# waves_v20.net
KiCad netlist of a schematic drawn in EAGLE
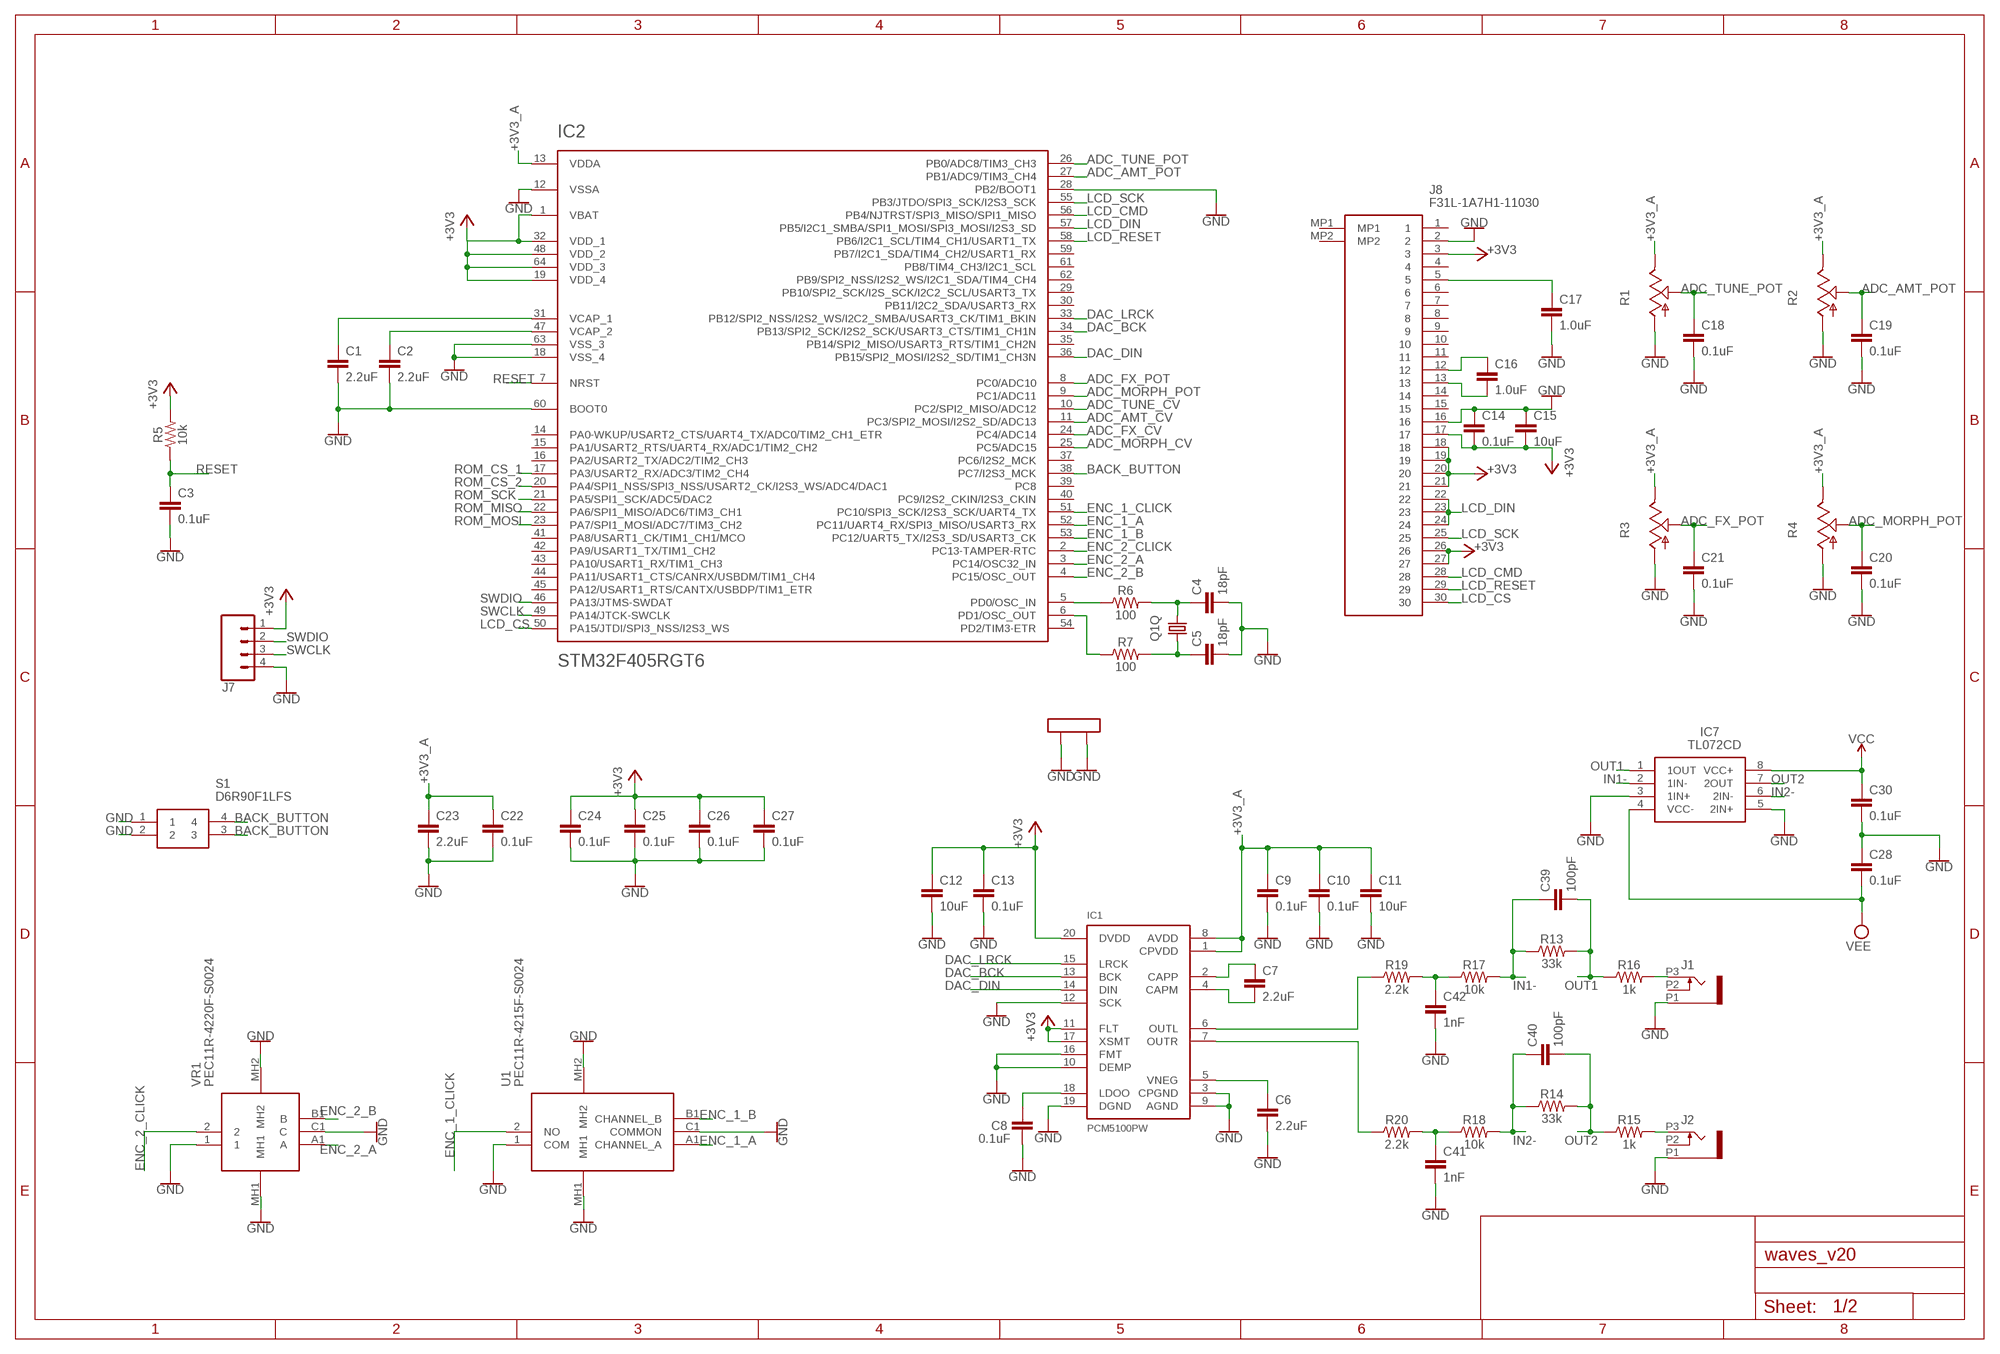
[diagram p0: schematic, sheet 1]
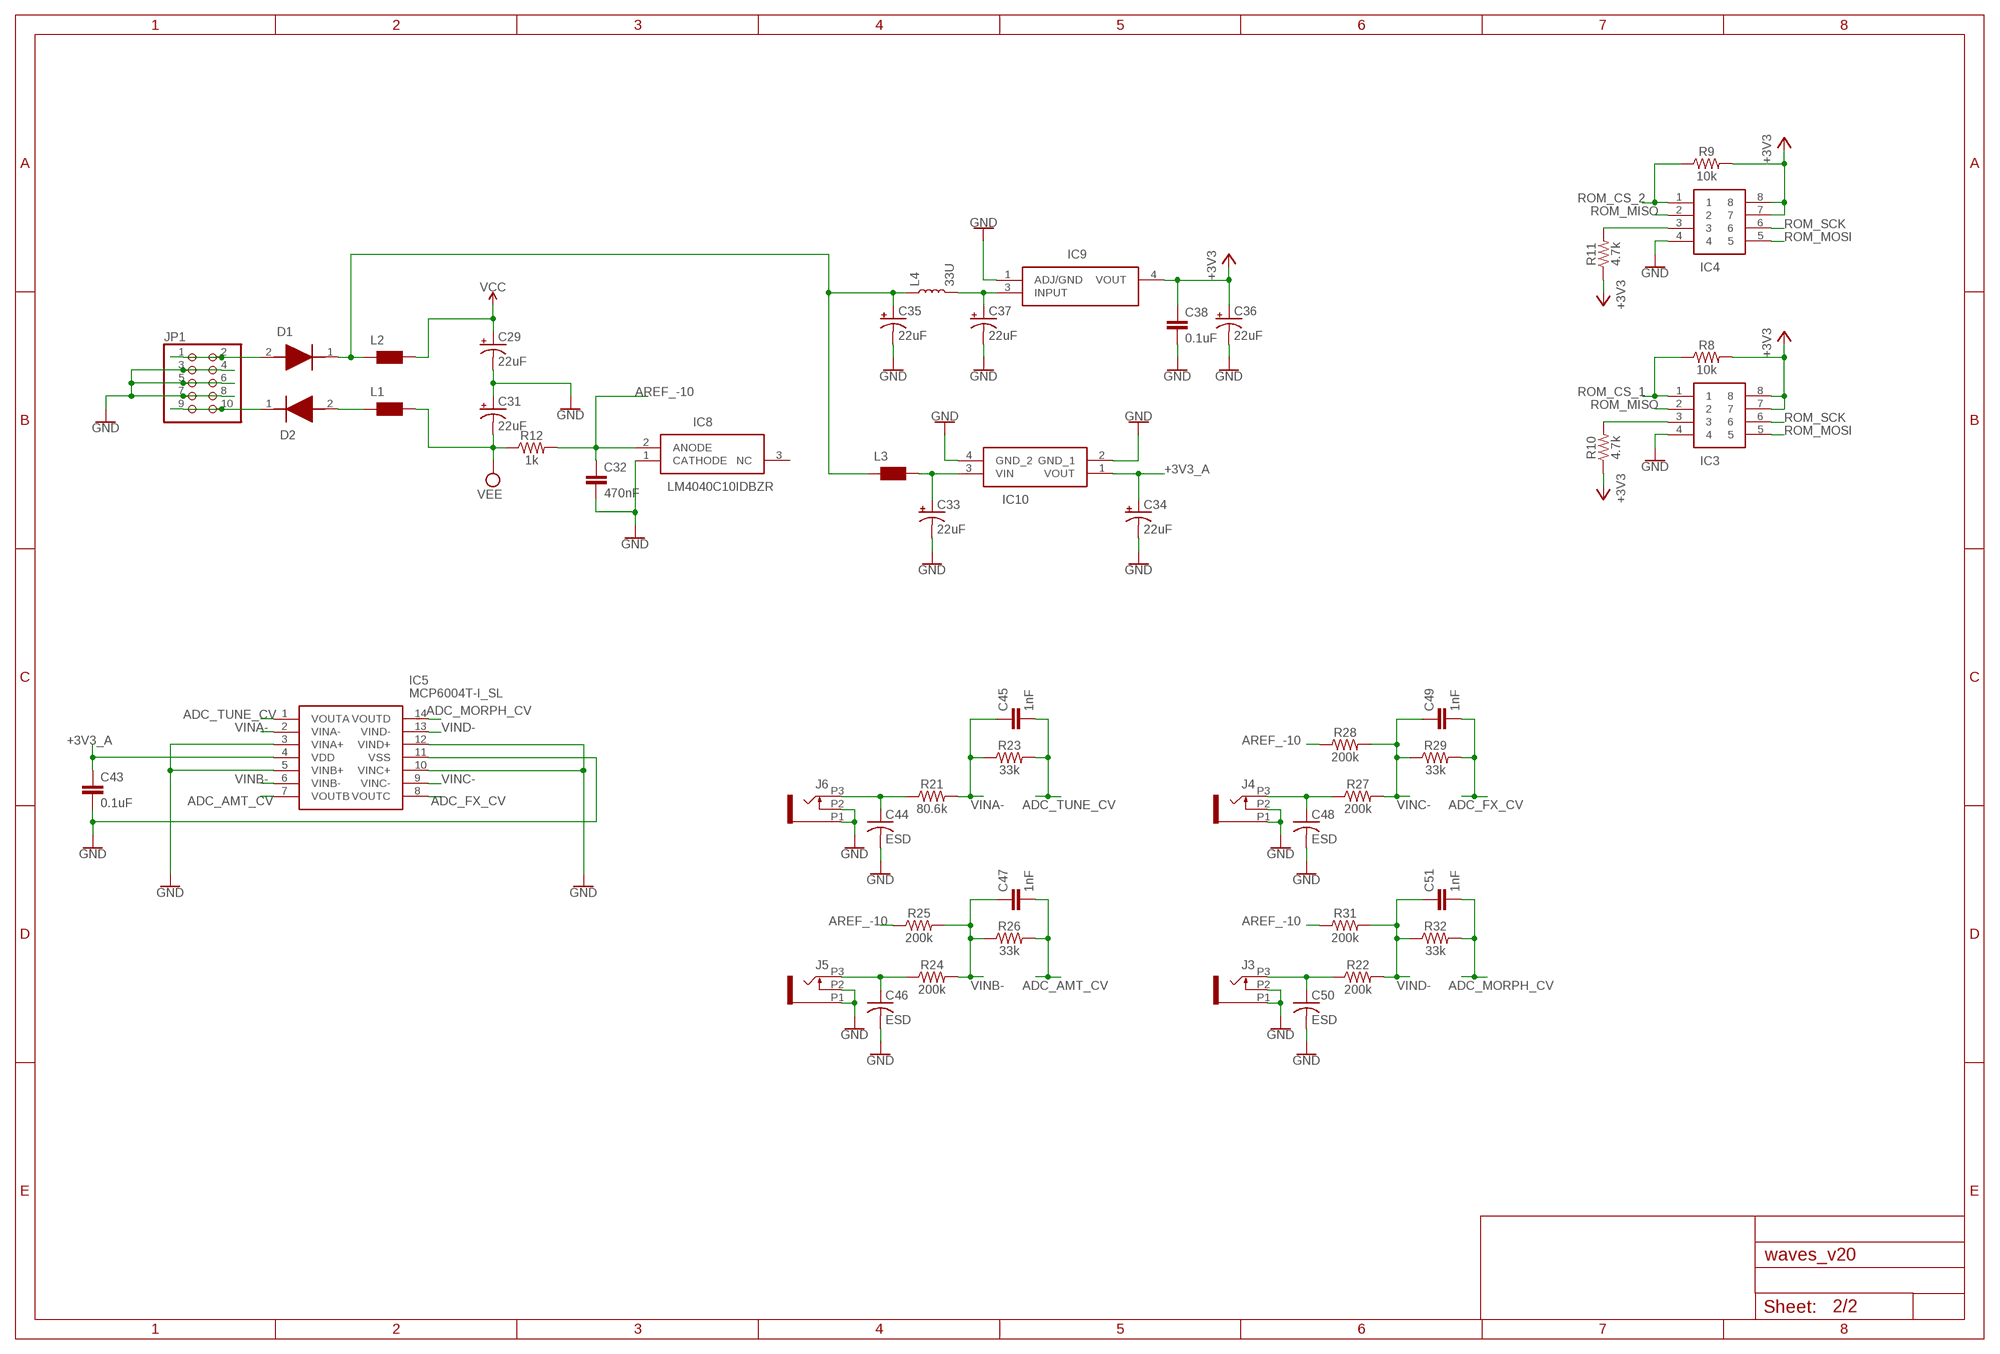
[diagram p1: schematic, sheet 2]

(export (version "E")
  (design (tool "Eeschema 10.0.6"))
  (components
    (comp (ref "C29")
      (value "22uF")
      (footprint "eagle-import:PANASONIC_C")
      (libsource (lib "eagle-import") (part "22UF-POLAR-PANASONIC_C-35V-20%"))
    )
    (comp (ref "C31")
      (value "22uF")
      (footprint "eagle-import:PANASONIC_C")
      (libsource (lib "eagle-import") (part "22UF-POLAR-PANASONIC_C-35V-20%"))
    )
    (comp (ref "C32")
      (value "470nF")
      (footprint "eagle-import:0402")
      (libsource (lib "eagle-import") (part "470NF-0402-16V-10%"))
    )
    (comp (ref "C33")
      (value "22uF")
      (footprint "eagle-import:PANASONIC_C")
      (libsource (lib "eagle-import") (part "22UF-POLAR-PANASONIC_C-35V-20%"))
    )
    (comp (ref "C34")
      (value "22uF")
      (footprint "eagle-import:PANASONIC_C")
      (libsource (lib "eagle-import") (part "22UF-POLAR-PANASONIC_C-35V-20%"))
    )
    (comp (ref "C35")
      (value "22uF")
      (footprint "eagle-import:PANASONIC_C")
      (libsource (lib "eagle-import") (part "22UF-POLAR-PANASONIC_C-35V-20%"))
    )
    (comp (ref "C36")
      (value "22uF")
      (footprint "eagle-import:PANASONIC_C")
      (libsource (lib "eagle-import") (part "22UF-POLAR-PANASONIC_C-35V-20%"))
    )
    (comp (ref "C37")
      (value "22uF")
      (footprint "eagle-import:PANASONIC_C")
      (libsource (lib "eagle-import") (part "22UF-POLAR-PANASONIC_C-35V-20%"))
    )
    (comp (ref "C38")
      (value "0.1uF")
      (footprint "eagle-import:0603")
      (libsource (lib "eagle-import") (part "0.1UF-0603-25V-(+80/-20%)"))
    )
    (comp (ref "C43")
      (value "0.1uF")
      (footprint "eagle-import:0603")
      (libsource (lib "eagle-import") (part "0.1UF-0603-25V-(+80/-20%)"))
    )
    (comp (ref "C44")
      (value "ESD")
      (footprint "eagle-import:C0603")
      (libsource (lib "eagle-import") (part "C-USC0603"))
    )
    (comp (ref "C45")
      (value "1nF")
      (footprint "eagle-import:0603")
      (libsource (lib "eagle-import") (part "1.0NF/1000PF-0603-50V-10%"))
    )
    (comp (ref "C46")
      (value "ESD")
      (footprint "eagle-import:C0603")
      (libsource (lib "eagle-import") (part "C-USC0603"))
    )
    (comp (ref "C47")
      (value "1nF")
      (footprint "eagle-import:0603")
      (libsource (lib "eagle-import") (part "1.0NF/1000PF-0603-50V-10%"))
    )
    (comp (ref "C48")
      (value "ESD")
      (footprint "eagle-import:C0603")
      (libsource (lib "eagle-import") (part "C-USC0603"))
    )
    (comp (ref "C49")
      (value "1nF")
      (footprint "eagle-import:0603")
      (libsource (lib "eagle-import") (part "1.0NF/1000PF-0603-50V-10%"))
    )
    (comp (ref "C50")
      (value "ESD")
      (footprint "eagle-import:C0603")
      (libsource (lib "eagle-import") (part "C-USC0603"))
    )
    (comp (ref "C51")
      (value "1nF")
      (footprint "eagle-import:0603")
      (libsource (lib "eagle-import") (part "1.0NF/1000PF-0603-50V-10%"))
    )
    (comp (ref "D1")
      (value "1N5819HW-7-F")
      (footprint "eagle-import:SOD3716X145N")
      (fields (field (name "MOUSER_PART_NUMBER") "621-1N5819HW-F"))
      (libsource (lib "eagle-import") (part "1N5819HW-7-F"))
    )
    (comp (ref "D2")
      (value "1N5819HW-7-F")
      (footprint "eagle-import:SOD3716X145N")
      (fields (field (name "MOUSER_PART_NUMBER") "621-1N5819HW-F"))
      (libsource (lib "eagle-import") (part "1N5819HW-7-F"))
    )
    (comp (ref "IC3")
      (value "1-2199298-2")
      (footprint "eagle-import:DIPS762W70P254L1016H510Q8N")
      (fields (field (name "MOUSER_PART_NUMBER") "571-1-2199298-2"))
      (libsource (lib "eagle-import") (part "1-2199298-2"))
    )
    (comp (ref "IC4")
      (value "1-2199298-2")
      (footprint "eagle-import:DIPS762W70P254L1016H510Q8N")
      (fields (field (name "MOUSER_PART_NUMBER") "571-1-2199298-2"))
      (libsource (lib "eagle-import") (part "1-2199298-2"))
    )
    (comp (ref "IC5")
      (value "MCP6004T-I_SL")
      (footprint "eagle-import:SOIC127P600X175-14N")
      (fields
        (field (name "MANUFACTURER_PART_NUMBER") "MCP6004T-I/SL")
        (field (name "MOUSER_PART_NUMBER") "579-MCP6004T-I/SL")
      )
      (libsource (lib "eagle-import") (part "MCP6004T-I_SL"))
    )
    (comp (ref "IC8")
      (value "LM4040C10IDBZR")
      (footprint "eagle-import:SOT95P237X112-3N")
      (fields (field (name "MOUSER_PART_NUMBER") "595-LM4040C10IDBZR"))
      (libsource (lib "eagle-import") (part "LM4040C10IDBZR"))
    )
    (comp (ref "IC9")
      (value "LM1117DT-3.3_NOPB")
      (footprint "eagle-import:TO228P991X238-3N")
      (fields
        (field (name "MANUFACTURER_PART_NUMBER") "LM1117DT-3.3/NOPB")
        (field (name "MOUSER_PART_NUMBER") "926-LM1117DT-3.3NOPB")
      )
      (libsource (lib "eagle-import") (part "LM1117DT-3.3_NOPB"))
    )
    (comp (ref "IC10")
      (value "LD2981ABU33TR")
      (footprint "eagle-import:LD2981ABU33TR")
      (fields (field (name "MOUSER_PART_NUMBER") "511-LD2981ABU33"))
      (libsource (lib "eagle-import") (part "LD2981ABU33TR"))
    )
    (comp (ref "J3")
      (value "PJ301_THONKICONN6")
      (footprint "eagle-import:WQP_PJ_301M6")
      (libsource (lib "eagle-import") (part "PJ301_THONKICONN6"))
    )
    (comp (ref "J4")
      (value "PJ301_THONKICONN6")
      (footprint "eagle-import:WQP_PJ_301M6")
      (libsource (lib "eagle-import") (part "PJ301_THONKICONN6"))
    )
    (comp (ref "J5")
      (value "PJ301_THONKICONN6")
      (footprint "eagle-import:WQP_PJ_301M6")
      (libsource (lib "eagle-import") (part "PJ301_THONKICONN6"))
    )
    (comp (ref "J6")
      (value "PJ301_THONKICONN6")
      (footprint "eagle-import:WQP_PJ_301M6")
      (libsource (lib "eagle-import") (part "PJ301_THONKICONN6"))
    )
    (comp (ref "JP1")
      (value "PINHD-2X5")
      (footprint "eagle-import:2X05")
      (libsource (lib "eagle-import") (part "PINHD-2X5"))
    )
    (comp (ref "L1")
      (value "WE-CBF_0603")
      (footprint "eagle-import:0603")
      (libsource (lib "eagle-import") (part "WE-CBF_0603"))
    )
    (comp (ref "L2")
      (value "WE-CBF_0603")
      (footprint "eagle-import:0603")
      (libsource (lib "eagle-import") (part "WE-CBF_0603"))
    )
    (comp (ref "L3")
      (value "WE-CBF_0603")
      (footprint "eagle-import:0603")
      (libsource (lib "eagle-import") (part "WE-CBF_0603"))
    )
    (comp (ref "L4")
      (value "33U")
      (footprint "eagle-import:0805")
      (libsource (lib "eagle-import") (part "INDUCTOR-0805-3.3UH"))
    )
    (comp (ref "R8")
      (value "10k")
      (footprint "eagle-import:0603")
      (libsource (lib "eagle-import") (part "10KOHM-0603-1/10W-1%"))
    )
    (comp (ref "R9")
      (value "10k")
      (footprint "eagle-import:0603")
      (libsource (lib "eagle-import") (part "10KOHM-0603-1/10W-1%"))
    )
    (comp (ref "R10")
      (value "4.7k")
      (footprint "eagle-import:0603")
      (libsource (lib "eagle-import") (part "4.7KOHM-0603-1/10W-1%"))
    )
    (comp (ref "R11")
      (value "4.7k")
      (footprint "eagle-import:0603")
      (libsource (lib "eagle-import") (part "4.7KOHM-0603-1/10W-1%"))
    )
    (comp (ref "R12")
      (value "1k")
      (footprint "eagle-import:0603")
      (libsource (lib "eagle-import") (part "1KOHM-0603-1/10W-1%"))
    )
    (comp (ref "R21")
      (value "80.6k")
      (footprint "eagle-import:0603")
      (libsource (lib "eagle-import") (part "82OHM-0603-1/10W-1%"))
    )
    (comp (ref "R22")
      (value "200k")
      (footprint "eagle-import:0603")
      (libsource (lib "eagle-import") (part "200KOHM-0603-1/10W-1%"))
    )
    (comp (ref "R23")
      (value "33k")
      (footprint "eagle-import:0603")
      (libsource (lib "eagle-import") (part "33KOHM-0603-1/10W-1%"))
    )
    (comp (ref "R24")
      (value "200k")
      (footprint "eagle-import:0603")
      (libsource (lib "eagle-import") (part "200KOHM-0603-1/10W-1%"))
    )
    (comp (ref "R25")
      (value "200k")
      (footprint "eagle-import:0603")
      (libsource (lib "eagle-import") (part "200KOHM-0603-1/10W-1%"))
    )
    (comp (ref "R26")
      (value "33k")
      (footprint "eagle-import:0603")
      (libsource (lib "eagle-import") (part "33KOHM-0603-1/10W-1%"))
    )
    (comp (ref "R27")
      (value "200k")
      (footprint "eagle-import:0603")
      (libsource (lib "eagle-import") (part "200KOHM-0603-1/10W-1%"))
    )
    (comp (ref "R28")
      (value "200k")
      (footprint "eagle-import:0603")
      (libsource (lib "eagle-import") (part "200KOHM-0603-1/10W-1%"))
    )
    (comp (ref "R29")
      (value "33k")
      (footprint "eagle-import:0603")
      (libsource (lib "eagle-import") (part "33KOHM-0603-1/10W-1%"))
    )
    (comp (ref "R31")
      (value "200k")
      (footprint "eagle-import:0603")
      (libsource (lib "eagle-import") (part "200KOHM-0603-1/10W-1%"))
    )
    (comp (ref "R32")
      (value "33k")
      (footprint "eagle-import:0603")
      (libsource (lib "eagle-import") (part "33KOHM-0603-1/10W-1%"))
    )
    (comp (ref "C1")
      (value "2.2uF")
      (footprint "eagle-import:0603")
      (libsource (lib "eagle-import") (part "2.2UF-0603-10V-20%"))
    )
    (comp (ref "C2")
      (value "2.2uF")
      (footprint "eagle-import:0603")
      (libsource (lib "eagle-import") (part "2.2UF-0603-10V-20%"))
    )
    (comp (ref "C3")
      (value "0.1uF")
      (footprint "eagle-import:0603")
      (libsource (lib "eagle-import") (part "0.1UF-0603-25V-(+80/-20%)"))
    )
    (comp (ref "C4")
      (value "18pF")
      (footprint "eagle-import:0603")
      (libsource (lib "eagle-import") (part "18PF-0603-50V-5%"))
    )
    (comp (ref "C5")
      (value "18pF")
      (footprint "eagle-import:0603")
      (libsource (lib "eagle-import") (part "18PF-0603-50V-5%"))
    )
    (comp (ref "C6")
      (value "2.2uF")
      (footprint "eagle-import:0603")
      (libsource (lib "eagle-import") (part "2.2UF-0603-10V-20%"))
    )
    (comp (ref "C7")
      (value "2.2uF")
      (footprint "eagle-import:0603")
      (libsource (lib "eagle-import") (part "2.2UF-0603-10V-20%"))
    )
    (comp (ref "C8")
      (value "0.1uF")
      (footprint "eagle-import:0603")
      (libsource (lib "eagle-import") (part "0.1UF-0603-25V-(+80/-20%)"))
    )
    (comp (ref "C9")
      (value "0.1uF")
      (footprint "eagle-import:0603")
      (libsource (lib "eagle-import") (part "0.1UF-0603-25V-(+80/-20%)"))
    )
    (comp (ref "C10")
      (value "0.1uF")
      (footprint "eagle-import:0603")
      (libsource (lib "eagle-import") (part "0.1UF-0603-25V-(+80/-20%)"))
    )
    (comp (ref "C11")
      (value "10uF")
      (footprint "eagle-import:0603")
      (libsource (lib "eagle-import") (part "10UF-0603-6.3V-20%"))
    )
    (comp (ref "C12")
      (value "10uF")
      (footprint "eagle-import:0603")
      (libsource (lib "eagle-import") (part "10UF-0603-6.3V-20%"))
    )
    (comp (ref "C13")
      (value "0.1uF")
      (footprint "eagle-import:0603")
      (libsource (lib "eagle-import") (part "0.1UF-0603-25V-(+80/-20%)"))
    )
    (comp (ref "C14")
      (value "0.1uF")
      (footprint "eagle-import:0603")
      (libsource (lib "eagle-import") (part "0.1UF-0603-25V-(+80/-20%)"))
    )
    (comp (ref "C15")
      (value "10uF")
      (footprint "eagle-import:0603")
      (libsource (lib "eagle-import") (part "10UF-0603-6.3V-20%"))
    )
    (comp (ref "C16")
      (value "1.0uF")
      (footprint "eagle-import:0603")
      (libsource (lib "eagle-import") (part "1.0UF-0603-16V-10%"))
    )
    (comp (ref "C17")
      (value "1.0uF")
      (footprint "eagle-import:0603")
      (libsource (lib "eagle-import") (part "1.0UF-0603-16V-10%"))
    )
    (comp (ref "C18")
      (value "0.1uF")
      (footprint "eagle-import:0603")
      (libsource (lib "eagle-import") (part "0.1UF-0603-25V-(+80/-20%)"))
    )
    (comp (ref "C19")
      (value "0.1uF")
      (footprint "eagle-import:0603")
      (libsource (lib "eagle-import") (part "0.1UF-0603-25V-(+80/-20%)"))
    )
    (comp (ref "C20")
      (value "0.1uF")
      (footprint "eagle-import:0603")
      (libsource (lib "eagle-import") (part "0.1UF-0603-25V-(+80/-20%)"))
    )
    (comp (ref "C21")
      (value "0.1uF")
      (footprint "eagle-import:0603")
      (libsource (lib "eagle-import") (part "0.1UF-0603-25V-(+80/-20%)"))
    )
    (comp (ref "C22")
      (value "0.1uF")
      (footprint "eagle-import:0603")
      (libsource (lib "eagle-import") (part "0.1UF-0603-25V-(+80/-20%)"))
    )
    (comp (ref "C23")
      (value "2.2uF")
      (footprint "eagle-import:0603")
      (libsource (lib "eagle-import") (part "2.2UF-0603-10V-20%"))
    )
    (comp (ref "C24")
      (value "0.1uF")
      (footprint "eagle-import:0603")
      (libsource (lib "eagle-import") (part "0.1UF-0603-25V-(+80/-20%)"))
    )
    (comp (ref "C25")
      (value "0.1uF")
      (footprint "eagle-import:0603")
      (libsource (lib "eagle-import") (part "0.1UF-0603-25V-(+80/-20%)"))
    )
    (comp (ref "C26")
      (value "0.1uF")
      (footprint "eagle-import:0603")
      (libsource (lib "eagle-import") (part "0.1UF-0603-25V-(+80/-20%)"))
    )
    (comp (ref "C27")
      (value "0.1uF")
      (footprint "eagle-import:0603")
      (libsource (lib "eagle-import") (part "0.1UF-0603-25V-(+80/-20%)"))
    )
    (comp (ref "C28")
      (value "0.1uF")
      (footprint "eagle-import:0603")
      (libsource (lib "eagle-import") (part "0.1UF-0603-25V-(+80/-20%)"))
    )
    (comp (ref "C30")
      (value "0.1uF")
      (footprint "eagle-import:0603")
      (libsource (lib "eagle-import") (part "0.1UF-0603-25V-(+80/-20%)"))
    )
    (comp (ref "C39")
      (value "100pF")
      (footprint "eagle-import:0603")
      (libsource (lib "eagle-import") (part "100PF-0603-50V-5%"))
    )
    (comp (ref "C40")
      (value "100pF")
      (footprint "eagle-import:0603")
      (libsource (lib "eagle-import") (part "100PF-0603-50V-5%"))
    )
    (comp (ref "C41")
      (value "1nF")
      (footprint "eagle-import:0603")
      (libsource (lib "eagle-import") (part "1.0NF/1000PF-0603-50V-10%"))
    )
    (comp (ref "C42")
      (value "1nF")
      (footprint "eagle-import:0603")
      (libsource (lib "eagle-import") (part "1.0NF/1000PF-0603-50V-10%"))
    )
    (comp (ref "IC1")
      (value "PCM5100PW")
      (footprint "eagle-import:SSOP20")
      (libsource (lib "eagle-import") (part "PCM5100PW"))
    )
    (comp (ref "IC2")
      (value "STM32F405RGT6")
      (footprint "eagle-import:TQFP-10X10-64")
      (libsource (lib "eagle-import") (part "STM32F20X"))
    )
    (comp (ref "IC7")
      (value "TL072CD")
      (footprint "eagle-import:SOIC127P600X175-8N")
      (fields (field (name "MOUSER_PART_NUMBER") "595-TL072CD"))
      (libsource (lib "eagle-import") (part "TL072CD"))
    )
    (comp (ref "J1")
      (value "PJ301_THONKICONN6")
      (footprint "eagle-import:WQP_PJ_301M6")
      (libsource (lib "eagle-import") (part "PJ301_THONKICONN6"))
    )
    (comp (ref "J2")
      (value "PJ301_THONKICONN6")
      (footprint "eagle-import:WQP_PJ_301M6")
      (libsource (lib "eagle-import") (part "PJ301_THONKICONN6"))
    )
    (comp (ref "J7")
      (value "CONN_04")
      (footprint "eagle-import:1X04")
      (libsource (lib "eagle-import") (part "CONN_04"))
    )
    (comp (ref "J8")
      (value "F31L-1A7H1-11030")
      (footprint "eagle-import:F31L1A7H111030")
      (fields (field (name "MOUSER_PART_NUMBER") "649-F31L-1A7H1-11030"))
      (libsource (lib "eagle-import") (part "F31L-1A7H1-11030"))
    )
    (comp (ref "Q1")
      (value "CRYSTAL")
      (footprint "eagle-import:CTS406")
      (libsource (lib "eagle-import") (part "CRYSTAL"))
    )
    (comp (ref "R1")
      (value "POT_USVERTICAL_PS")
      (footprint "eagle-import:ALPS_POT_VERTICAL_PS")
      (libsource (lib "eagle-import") (part "POT_USVERTICAL_PS"))
    )
    (comp (ref "R2")
      (value "POT_USVERTICAL_PS")
      (footprint "eagle-import:ALPS_POT_VERTICAL_PS")
      (libsource (lib "eagle-import") (part "POT_USVERTICAL_PS"))
    )
    (comp (ref "R3")
      (value "POT_USVERTICAL_PS")
      (footprint "eagle-import:ALPS_POT_VERTICAL_PS")
      (libsource (lib "eagle-import") (part "POT_USVERTICAL_PS"))
    )
    (comp (ref "R4")
      (value "POT_USVERTICAL_PS")
      (footprint "eagle-import:ALPS_POT_VERTICAL_PS")
      (libsource (lib "eagle-import") (part "POT_USVERTICAL_PS"))
    )
    (comp (ref "R5")
      (value "10k")
      (footprint "eagle-import:0603")
      (libsource (lib "eagle-import") (part "10KOHM-0603-1/10W-1%"))
    )
    (comp (ref "R6")
      (value "100")
      (footprint "eagle-import:0603")
      (libsource (lib "eagle-import") (part "100OHM-0603-1/10W-1%"))
    )
    (comp (ref "R7")
      (value "100")
      (footprint "eagle-import:0603")
      (libsource (lib "eagle-import") (part "100OHM-0603-1/10W-1%"))
    )
    (comp (ref "R13")
      (value "33k")
      (footprint "eagle-import:0603")
      (libsource (lib "eagle-import") (part "33KOHM-0603-1/10W-1%"))
    )
    (comp (ref "R14")
      (value "33k")
      (footprint "eagle-import:0603")
      (libsource (lib "eagle-import") (part "33KOHM-0603-1/10W-1%"))
    )
    (comp (ref "R15")
      (value "1k")
      (footprint "eagle-import:0603")
      (libsource (lib "eagle-import") (part "1KOHM-0603-1/10W-1%"))
    )
    (comp (ref "R16")
      (value "1k")
      (footprint "eagle-import:0603")
      (libsource (lib "eagle-import") (part "1KOHM-0603-1/10W-1%"))
    )
    (comp (ref "R17")
      (value "10k")
      (footprint "eagle-import:0603")
      (libsource (lib "eagle-import") (part "10KOHM-0603-1/10W-1%"))
    )
    (comp (ref "R18")
      (value "10k")
      (footprint "eagle-import:0603")
      (libsource (lib "eagle-import") (part "10KOHM-0603-1/10W-1%"))
    )
    (comp (ref "R19")
      (value "2.2k")
      (footprint "eagle-import:0603")
      (libsource (lib "eagle-import") (part "2.2KOHM-0603-1/10W-1%"))
    )
    (comp (ref "R20")
      (value "2.2k")
      (footprint "eagle-import:0603")
      (libsource (lib "eagle-import") (part "2.2KOHM-0603-1/10W-1%"))
    )
    (comp (ref "S1")
      (value "D6R90F1LFS")
      (footprint "eagle-import:D6C10F1LFS")
      (fields (field (name "MOUSER_PART_NUMBER") "611-D6R90LFS"))
      (libsource (lib "eagle-import") (part "D6R90F1LFS"))
    )
    (comp (ref "U1")
      (value "PEC11R-4215F-S0024")
      (footprint "eagle-import:PEC11R4215FS0024")
      (fields (field (name "MOUSER_PART_NUMBER") "652-PEC11R-4215F-S24"))
      (libsource (lib "eagle-import") (part "PEC11R-4215F-S0024"))
    )
    (comp (ref "VR1")
      (value "PEC11R-4220F-S0024")
      (footprint "eagle-import:PEC11R4220FS0024")
      (fields (field (name "MOUSER_PART_NUMBER") "652-PEC11R-4220F-S24"))
      (libsource (lib "eagle-import") (part "PEC11R-4220F-S0024"))
    )
  )
  (nets
    (net (code "1") (name "+3V3") (class "Default")
      (node (ref "C12") (pin "1") (pinfunction "1_1") (pintype "passive"))
      (node (ref "C13") (pin "1") (pinfunction "1_1") (pintype "passive"))
      (node (ref "C14") (pin "2") (pinfunction "2_2") (pintype "passive"))
      (node (ref "C15") (pin "2") (pinfunction "2_2") (pintype "passive"))
      (node (ref "C24") (pin "1") (pinfunction "1_1") (pintype "passive"))
      (node (ref "C25") (pin "1") (pinfunction "1_1") (pintype "passive"))
      (node (ref "C26") (pin "1") (pinfunction "1_1") (pintype "passive"))
      (node (ref "C27") (pin "1") (pinfunction "1_1") (pintype "passive"))
      (node (ref "C36") (pin "+") (pinfunction "+_+") (pintype "passive"))
      (node (ref "C38") (pin "1") (pinfunction "1_1") (pintype "passive"))
      (node (ref "IC1") (pin "11") (pinfunction "FLT_11") (pintype "input"))
      (node (ref "IC1") (pin "17") (pinfunction "XSMT_17") (pintype "input"))
      (node (ref "IC1") (pin "20") (pinfunction "DVDD_20") (pintype "power_in"))
      (node (ref "IC2") (pin "1") (pinfunction "VBAT_1") (pintype "power_in"))
      (node (ref "IC2") (pin "19") (pinfunction "VDD_4_19") (pintype "power_in"))
      (node (ref "IC2") (pin "32") (pinfunction "VDD_1_32") (pintype "power_in"))
      (node (ref "IC2") (pin "48") (pinfunction "VDD_2_48") (pintype "power_in"))
      (node (ref "IC2") (pin "64") (pinfunction "VDD_3_64") (pintype "power_in"))
      (node (ref "IC3") (pin "7") (pinfunction "7_7") (pintype "bidirectional"))
      (node (ref "IC3") (pin "8") (pinfunction "8_8") (pintype "bidirectional"))
      (node (ref "IC4") (pin "7") (pinfunction "7_7") (pintype "bidirectional"))
      (node (ref "IC4") (pin "8") (pinfunction "8_8") (pintype "bidirectional"))
      (node (ref "IC9") (pin "4") (pinfunction "VOUT_4") (pintype "output"))
      (node (ref "J7") (pin "1") (pinfunction "1_1") (pintype "passive"))
      (node (ref "J8") (pin "17") (pinfunction "17_17") (pintype "bidirectional"))
      (node (ref "J8") (pin "18") (pinfunction "18_18") (pintype "bidirectional"))
      (node (ref "J8") (pin "19") (pinfunction "19_19") (pintype "bidirectional"))
      (node (ref "J8") (pin "20") (pinfunction "20_20") (pintype "bidirectional"))
      (node (ref "J8") (pin "21") (pinfunction "21_21") (pintype "bidirectional"))
      (node (ref "J8") (pin "26") (pinfunction "26_26") (pintype "bidirectional"))
      (node (ref "J8") (pin "27") (pinfunction "27_27") (pintype "bidirectional"))
      (node (ref "J8") (pin "3") (pinfunction "3_3") (pintype "bidirectional"))
      (node (ref "R10") (pin "1") (pinfunction "1_1") (pintype "passive"))
      (node (ref "R11") (pin "1") (pinfunction "1_1") (pintype "passive"))
      (node (ref "R5") (pin "2") (pinfunction "2_2") (pintype "passive"))
      (node (ref "R8") (pin "2") (pinfunction "2_2") (pintype "passive"))
      (node (ref "R9") (pin "2") (pinfunction "2_2") (pintype "passive"))
    )
    (net (code "2") (name "+3V3_A") (class "Default")
      (node (ref "C10") (pin "1") (pinfunction "1_1") (pintype "passive"))
      (node (ref "C11") (pin "1") (pinfunction "1_1") (pintype "passive"))
      (node (ref "C22") (pin "1") (pinfunction "1_1") (pintype "passive"))
      (node (ref "C23") (pin "1") (pinfunction "1_1") (pintype "passive"))
      (node (ref "C34") (pin "+") (pinfunction "+_+") (pintype "passive"))
      (node (ref "C43") (pin "1") (pinfunction "1_1") (pintype "passive"))
      (node (ref "C9") (pin "1") (pinfunction "1_1") (pintype "passive"))
      (node (ref "IC1") (pin "1") (pinfunction "CPVDD_1") (pintype "bidirectional"))
      (node (ref "IC1") (pin "8") (pinfunction "AVDD_8") (pintype "power_in"))
      (node (ref "IC10") (pin "1") (pinfunction "VOUT_1") (pintype "bidirectional"))
      (node (ref "IC2") (pin "13") (pinfunction "VDDA_13") (pintype "power_in"))
      (node (ref "IC5") (pin "4") (pinfunction "VDD_4") (pintype "bidirectional"))
      (node (ref "R1") (pin "P$1") (pinfunction "E_P$1") (pintype "passive"))
      (node (ref "R2") (pin "P$1") (pinfunction "E_P$1") (pintype "passive"))
      (node (ref "R3") (pin "P$1") (pinfunction "E_P$1") (pintype "passive"))
      (node (ref "R4") (pin "P$1") (pinfunction "E_P$1") (pintype "passive"))
    )
    (net (code "3") (name "ADC_AMT_CV") (class "Default")
      (node (ref "C47") (pin "2") (pinfunction "2_2") (pintype "passive"))
      (node (ref "IC2") (pin "11") (pinfunction "PC3/SPI2_MOSI/I2S2_SD/ADC13_11") (pintype "bidirectional"))
      (node (ref "IC5") (pin "7") (pinfunction "VOUTB_7") (pintype "bidirectional"))
      (node (ref "R26") (pin "2") (pinfunction "2_2") (pintype "passive"))
    )
    (net (code "4") (name "ADC_AMT_POT") (class "Default")
      (node (ref "C19") (pin "1") (pinfunction "1_1") (pintype "passive"))
      (node (ref "IC2") (pin "27") (pinfunction "PB1/ADC9/TIM3_CH4_27") (pintype "bidirectional"))
      (node (ref "R2") (pin "P$2") (pinfunction "S_P$2") (pintype "passive"))
    )
    (net (code "5") (name "ADC_FX_CV") (class "Default")
      (node (ref "C49") (pin "2") (pinfunction "2_2") (pintype "passive"))
      (node (ref "IC2") (pin "24") (pinfunction "PC4/ADC14_24") (pintype "bidirectional"))
      (node (ref "IC5") (pin "8") (pinfunction "VOUTC_8") (pintype "bidirectional"))
      (node (ref "R29") (pin "2") (pinfunction "2_2") (pintype "passive"))
    )
    (net (code "6") (name "ADC_FX_POT") (class "Default")
      (node (ref "C21") (pin "1") (pinfunction "1_1") (pintype "passive"))
      (node (ref "IC2") (pin "8") (pinfunction "PC0/ADC10_8") (pintype "bidirectional"))
      (node (ref "R3") (pin "P$2") (pinfunction "S_P$2") (pintype "passive"))
    )
    (net (code "7") (name "ADC_MORPH_CV") (class "Default")
      (node (ref "C51") (pin "2") (pinfunction "2_2") (pintype "passive"))
      (node (ref "IC2") (pin "25") (pinfunction "PC5/ADC15_25") (pintype "bidirectional"))
      (node (ref "IC5") (pin "14") (pinfunction "VOUTD_14") (pintype "bidirectional"))
      (node (ref "R32") (pin "2") (pinfunction "2_2") (pintype "passive"))
    )
    (net (code "8") (name "ADC_MORPH_POT") (class "Default")
      (node (ref "C20") (pin "1") (pinfunction "1_1") (pintype "passive"))
      (node (ref "IC2") (pin "9") (pinfunction "PC1/ADC11_9") (pintype "bidirectional"))
      (node (ref "R4") (pin "P$2") (pinfunction "S_P$2") (pintype "passive"))
    )
    (net (code "9") (name "ADC_TUNE_CV") (class "Default")
      (node (ref "C45") (pin "2") (pinfunction "2_2") (pintype "passive"))
      (node (ref "IC2") (pin "10") (pinfunction "PC2/SPI2_MISO/ADC12_10") (pintype "bidirectional"))
      (node (ref "IC5") (pin "1") (pinfunction "VOUTA_1") (pintype "bidirectional"))
      (node (ref "R23") (pin "2") (pinfunction "2_2") (pintype "passive"))
    )
    (net (code "10") (name "ADC_TUNE_POT") (class "Default")
      (node (ref "C18") (pin "1") (pinfunction "1_1") (pintype "passive"))
      (node (ref "IC2") (pin "26") (pinfunction "PB0/ADC8/TIM3_CH3_26") (pintype "bidirectional"))
      (node (ref "R1") (pin "P$2") (pinfunction "S_P$2") (pintype "passive"))
    )
    (net (code "11") (name "AREF_-10") (class "Default")
      (node (ref "C32") (pin "1") (pinfunction "1_1") (pintype "passive"))
      (node (ref "IC8") (pin "2") (pinfunction "ANODE_2") (pintype "bidirectional"))
      (node (ref "R12") (pin "2") (pinfunction "2_2") (pintype "passive"))
      (node (ref "R25") (pin "1") (pinfunction "1_1") (pintype "passive"))
      (node (ref "R28") (pin "1") (pinfunction "1_1") (pintype "passive"))
      (node (ref "R31") (pin "1") (pinfunction "1_1") (pintype "passive"))
    )
    (net (code "12") (name "BACK_BUTTON") (class "Default")
      (node (ref "IC2") (pin "38") (pinfunction "PC7/I2S3_MCK_38") (pintype "bidirectional"))
      (node (ref "S1") (pin "3") (pinfunction "3_3") (pintype "bidirectional"))
      (node (ref "S1") (pin "4") (pinfunction "4_4") (pintype "bidirectional"))
    )
    (net (code "13") (name "DAC_BCK") (class "Default")
      (node (ref "IC1") (pin "13") (pinfunction "BCK_13") (pintype "input"))
      (node (ref "IC2") (pin "34") (pinfunction "PB13/SPI2_SCK/I2S2_SCK/USART3_CTS/TIM1_CH1N_34") (pintype "bidirectional"))
    )
    (net (code "14") (name "DAC_DIN") (class "Default")
      (node (ref "IC1") (pin "14") (pinfunction "DIN_14") (pintype "input"))
      (node (ref "IC2") (pin "36") (pinfunction "PB15/SPI2_MOSI/I2S2_SD/TIM1_CH3N_36") (pintype "bidirectional"))
    )
    (net (code "15") (name "DAC_LRCK") (class "Default")
      (node (ref "IC1") (pin "15") (pinfunction "LRCK_15") (pintype "input"))
      (node (ref "IC2") (pin "33") (pinfunction "PB12/SPI2_NSS/I2S2_WS/I2C2_SMBA/USART3_CK/TIM1_BKIN_33") (pintype "bidirectional"))
    )
    (net (code "16") (name "ENC_1_A") (class "Default")
      (node (ref "IC2") (pin "52") (pinfunction "PC11/UART4_RX/SPI3_MISO/USART3_RX_52") (pintype "bidirectional"))
      (node (ref "U1") (pin "A1") (pinfunction "CHANNEL_A_A1") (pintype "bidirectional"))
    )
    (net (code "17") (name "ENC_1_B") (class "Default")
      (node (ref "IC2") (pin "53") (pinfunction "PC12/UART5_TX/I2S3_SD/USART3_CK_53") (pintype "bidirectional"))
      (node (ref "U1") (pin "B1") (pinfunction "CHANNEL_B_B1") (pintype "bidirectional"))
    )
    (net (code "18") (name "ENC_1_CLICK") (class "Default")
      (node (ref "IC2") (pin "51") (pinfunction "PC10/SPI3_SCK/I2S3_SCK/UART4_TX_51") (pintype "bidirectional"))
      (node (ref "U1") (pin "2") (pinfunction "NO_2") (pintype "bidirectional"))
    )
    (net (code "19") (name "ENC_2_A") (class "Default")
      (node (ref "IC2") (pin "3") (pinfunction "PC14/OSC32_IN_3") (pintype "bidirectional"))
      (node (ref "VR1") (pin "A1") (pinfunction "A_A1") (pintype "bidirectional"))
    )
    (net (code "20") (name "ENC_2_B") (class "Default")
      (node (ref "IC2") (pin "4") (pinfunction "PC15/OSC_OUT_4") (pintype "bidirectional"))
      (node (ref "VR1") (pin "B1") (pinfunction "B_B1") (pintype "bidirectional"))
    )
    (net (code "21") (name "ENC_2_CLICK") (class "Default")
      (node (ref "IC2") (pin "2") (pinfunction "PC13-TAMPER-RTC_2") (pintype "bidirectional"))
      (node (ref "VR1") (pin "2") (pinfunction "2_2") (pintype "bidirectional"))
    )
    (net (code "22") (name "GND") (class "Default")
      (node (ref "C1") (pin "2") (pinfunction "2_2") (pintype "passive"))
      (node (ref "C10") (pin "2") (pinfunction "2_2") (pintype "passive"))
      (node (ref "C11") (pin "2") (pinfunction "2_2") (pintype "passive"))
      (node (ref "C12") (pin "2") (pinfunction "2_2") (pintype "passive"))
      (node (ref "C13") (pin "2") (pinfunction "2_2") (pintype "passive"))
      (node (ref "C14") (pin "1") (pinfunction "1_1") (pintype "passive"))
      (node (ref "C15") (pin "1") (pinfunction "1_1") (pintype "passive"))
      (node (ref "C17") (pin "2") (pinfunction "2_2") (pintype "passive"))
      (node (ref "C18") (pin "2") (pinfunction "2_2") (pintype "passive"))
      (node (ref "C19") (pin "2") (pinfunction "2_2") (pintype "passive"))
      (node (ref "C2") (pin "2") (pinfunction "2_2") (pintype "passive"))
      (node (ref "C20") (pin "2") (pinfunction "2_2") (pintype "passive"))
      (node (ref "C21") (pin "2") (pinfunction "2_2") (pintype "passive"))
      (node (ref "C22") (pin "2") (pinfunction "2_2") (pintype "passive"))
      (node (ref "C23") (pin "2") (pinfunction "2_2") (pintype "passive"))
      (node (ref "C24") (pin "2") (pinfunction "2_2") (pintype "passive"))
      (node (ref "C25") (pin "2") (pinfunction "2_2") (pintype "passive"))
      (node (ref "C26") (pin "2") (pinfunction "2_2") (pintype "passive"))
      (node (ref "C27") (pin "2") (pinfunction "2_2") (pintype "passive"))
      (node (ref "C28") (pin "1") (pinfunction "1_1") (pintype "passive"))
      (node (ref "C29") (pin "-") (pinfunction "-_-") (pintype "passive"))
      (node (ref "C3") (pin "2") (pinfunction "2_2") (pintype "passive"))
      (node (ref "C30") (pin "2") (pinfunction "2_2") (pintype "passive"))
      (node (ref "C31") (pin "+") (pinfunction "+_+") (pintype "passive"))
      (node (ref "C32") (pin "2") (pinfunction "2_2") (pintype "passive"))
      (node (ref "C33") (pin "-") (pinfunction "-_-") (pintype "passive"))
      (node (ref "C34") (pin "-") (pinfunction "-_-") (pintype "passive"))
      (node (ref "C35") (pin "-") (pinfunction "-_-") (pintype "passive"))
      (node (ref "C36") (pin "-") (pinfunction "-_-") (pintype "passive"))
      (node (ref "C37") (pin "-") (pinfunction "-_-") (pintype "passive"))
      (node (ref "C38") (pin "2") (pinfunction "2_2") (pintype "passive"))
      (node (ref "C4") (pin "2") (pinfunction "2_2") (pintype "passive"))
      (node (ref "C41") (pin "2") (pinfunction "2_2") (pintype "passive"))
      (node (ref "C42") (pin "2") (pinfunction "2_2") (pintype "passive"))
      (node (ref "C43") (pin "2") (pinfunction "2_2") (pintype "passive"))
      (node (ref "C44") (pin "2") (pinfunction "2_2") (pintype "passive"))
      (node (ref "C46") (pin "2") (pinfunction "2_2") (pintype "passive"))
      (node (ref "C48") (pin "2") (pinfunction "2_2") (pintype "passive"))
      (node (ref "C5") (pin "2") (pinfunction "2_2") (pintype "passive"))
      (node (ref "C50") (pin "2") (pinfunction "2_2") (pintype "passive"))
      (node (ref "C6") (pin "2") (pinfunction "2_2") (pintype "passive"))
      (node (ref "C8") (pin "2") (pinfunction "2_2") (pintype "passive"))
      (node (ref "C9") (pin "2") (pinfunction "2_2") (pintype "passive"))
      (node (ref "IC1") (pin "10") (pinfunction "DEMP_10") (pintype "input"))
      (node (ref "IC1") (pin "12") (pinfunction "SCK_12") (pintype "input"))
      (node (ref "IC1") (pin "16") (pinfunction "FMT_16") (pintype "input"))
      (node (ref "IC1") (pin "19") (pinfunction "DGND_19") (pintype "power_in"))
      (node (ref "IC1") (pin "3") (pinfunction "CPGND_3") (pintype "bidirectional"))
      (node (ref "IC1") (pin "9") (pinfunction "AGND_9") (pintype "power_in"))
      (node (ref "IC10") (pin "2") (pinfunction "GND_1_2") (pintype "bidirectional"))
      (node (ref "IC10") (pin "4") (pinfunction "GND_2_4") (pintype "bidirectional"))
      (node (ref "IC2") (pin "12") (pinfunction "VSSA_12") (pintype "power_in"))
      (node (ref "IC2") (pin "18") (pinfunction "VSS_4_18") (pintype "power_in"))
      (node (ref "IC2") (pin "28") (pinfunction "PB2/BOOT1_28") (pintype "bidirectional"))
      (node (ref "IC2") (pin "60") (pinfunction "BOOT0_60") (pintype "bidirectional"))
      (node (ref "IC2") (pin "63") (pinfunction "VSS_3_63") (pintype "power_in"))
      (node (ref "IC3") (pin "4") (pinfunction "4_4") (pintype "bidirectional"))
      (node (ref "IC4") (pin "4") (pinfunction "4_4") (pintype "bidirectional"))
      (node (ref "IC5") (pin "10") (pinfunction "VINC+_10") (pintype "bidirectional"))
      (node (ref "IC5") (pin "11") (pinfunction "VSS_11") (pintype "bidirectional"))
      (node (ref "IC5") (pin "12") (pinfunction "VIND+_12") (pintype "bidirectional"))
      (node (ref "IC5") (pin "3") (pinfunction "VINA+_3") (pintype "bidirectional"))
      (node (ref "IC5") (pin "5") (pinfunction "VINB+_5") (pintype "bidirectional"))
      (node (ref "IC7") (pin "3") (pinfunction "1IN+_3") (pintype "bidirectional"))
      (node (ref "IC7") (pin "5") (pinfunction "2IN+_5") (pintype "bidirectional"))
      (node (ref "IC8") (pin "1") (pinfunction "CATHODE_1") (pintype "bidirectional"))
      (node (ref "IC9") (pin "1") (pinfunction "ADJ/GND_1") (pintype "power_in"))
      (node (ref "J1") (pin "P1") (pinfunction "1_P1") (pintype "passive"))
      (node (ref "J2") (pin "P1") (pinfunction "1_P1") (pintype "passive"))
      (node (ref "J3") (pin "P1") (pinfunction "1_P1") (pintype "passive"))
      (node (ref "J3") (pin "P2") (pinfunction "2_P2") (pintype "passive"))
      (node (ref "J4") (pin "P1") (pinfunction "1_P1") (pintype "passive"))
      (node (ref "J4") (pin "P2") (pinfunction "2_P2") (pintype "passive"))
      (node (ref "J5") (pin "P1") (pinfunction "1_P1") (pintype "passive"))
      (node (ref "J5") (pin "P2") (pinfunction "2_P2") (pintype "passive"))
      (node (ref "J6") (pin "P1") (pinfunction "1_P1") (pintype "passive"))
      (node (ref "J6") (pin "P2") (pinfunction "2_P2") (pintype "passive"))
      (node (ref "J7") (pin "4") (pinfunction "4_4") (pintype "passive"))
      (node (ref "J8") (pin "16") (pinfunction "16_16") (pintype "bidirectional"))
      (node (ref "J8") (pin "2") (pinfunction "2_2") (pintype "bidirectional"))
      (node (ref "JP1") (pin "3") (pinfunction "3_3") (pintype "passive"))
      (node (ref "JP1") (pin "4") (pinfunction "4_4") (pintype "passive"))
      (node (ref "JP1") (pin "5") (pinfunction "5_5") (pintype "passive"))
      (node (ref "JP1") (pin "6") (pinfunction "6_6") (pintype "passive"))
      (node (ref "JP1") (pin "7") (pinfunction "7_7") (pintype "passive"))
      (node (ref "JP1") (pin "8") (pinfunction "8_8") (pintype "passive"))
      (node (ref "Q1") (pin "2") (pinfunction "LID1_2") (pintype "power_in"))
      (node (ref "Q1") (pin "4") (pinfunction "LID2_4") (pintype "power_in"))
      (node (ref "R1") (pin "P$3") (pinfunction "A_P$3") (pintype "passive"))
      (node (ref "R2") (pin "P$3") (pinfunction "A_P$3") (pintype "passive"))
      (node (ref "R3") (pin "P$3") (pinfunction "A_P$3") (pintype "passive"))
      (node (ref "R4") (pin "P$3") (pinfunction "A_P$3") (pintype "passive"))
      (node (ref "S1") (pin "1") (pinfunction "1_1") (pintype "bidirectional"))
      (node (ref "S1") (pin "2") (pinfunction "2_2") (pintype "bidirectional"))
      (node (ref "U1") (pin "1") (pinfunction "COM_1") (pintype "bidirectional"))
      (node (ref "U1") (pin "C1") (pinfunction "COMMON_C1") (pintype "bidirectional"))
      (node (ref "U1") (pin "MH1") (pinfunction "MH1_MH1") (pintype "bidirectional"))
      (node (ref "U1") (pin "MH2") (pinfunction "MH2_MH2") (pintype "bidirectional"))
      (node (ref "VR1") (pin "1") (pinfunction "1_1") (pintype "bidirectional"))
      (node (ref "VR1") (pin "C1") (pinfunction "C_C1") (pintype "bidirectional"))
      (node (ref "VR1") (pin "MH1") (pinfunction "MH1_MH1") (pintype "bidirectional"))
      (node (ref "VR1") (pin "MH2") (pinfunction "MH2_MH2") (pintype "bidirectional"))
    )
    (net (code "23") (name "IN1-") (class "Default")
      (node (ref "C39") (pin "1") (pinfunction "1_1") (pintype "passive"))
      (node (ref "IC7") (pin "2") (pinfunction "1IN-_2") (pintype "bidirectional"))
      (node (ref "R13") (pin "1") (pinfunction "1_1") (pintype "passive"))
      (node (ref "R17") (pin "2") (pinfunction "2_2") (pintype "passive"))
    )
    (net (code "24") (name "IN2-") (class "Default")
      (node (ref "C40") (pin "1") (pinfunction "1_1") (pintype "passive"))
      (node (ref "IC7") (pin "6") (pinfunction "2IN-_6") (pintype "bidirectional"))
      (node (ref "R14") (pin "1") (pinfunction "1_1") (pintype "passive"))
      (node (ref "R18") (pin "2") (pinfunction "2_2") (pintype "passive"))
    )
    (net (code "25") (name "LCD_CMD") (class "Default")
      (node (ref "IC2") (pin "56") (pinfunction "PB4/NJTRST/SPI3_MISO/SPI1_MISO_56") (pintype "bidirectional"))
      (node (ref "J8") (pin "28") (pinfunction "28_28") (pintype "bidirectional"))
    )
    (net (code "26") (name "LCD_CS") (class "Default")
      (node (ref "IC2") (pin "50") (pinfunction "PA15/JTDI/SPI3_NSS/I2S3_WS_50") (pintype "bidirectional"))
      (node (ref "J8") (pin "30") (pinfunction "30_30") (pintype "bidirectional"))
    )
    (net (code "27") (name "LCD_DIN") (class "Default")
      (node (ref "IC2") (pin "57") (pinfunction "PB5/I2C1_SMBA/SPI1_MOSI/SPI3_MOSI/I2S3_SD_57") (pintype "bidirectional"))
      (node (ref "J8") (pin "22") (pinfunction "22_22") (pintype "bidirectional"))
      (node (ref "J8") (pin "23") (pinfunction "23_23") (pintype "bidirectional"))
      (node (ref "J8") (pin "24") (pinfunction "24_24") (pintype "bidirectional"))
    )
    (net (code "28") (name "LCD_RESET") (class "Default")
      (node (ref "IC2") (pin "58") (pinfunction "PB6/I2C1_SCL/TIM4_CH1/USART1_TX_58") (pintype "bidirectional"))
      (node (ref "J8") (pin "29") (pinfunction "29_29") (pintype "bidirectional"))
    )
    (net (code "29") (name "LCD_SCK") (class "Default")
      (node (ref "IC2") (pin "55") (pinfunction "PB3/JTDO/SPI3_SCK/I2S3_SCK_55") (pintype "bidirectional"))
      (node (ref "J8") (pin "25") (pinfunction "25_25") (pintype "bidirectional"))
    )
    (net (code "30") (name "Net-(C5-Pad1)") (class "Default")
      (node (ref "C5") (pin "1") (pinfunction "1_1") (pintype "passive"))
      (node (ref "Q1") (pin "1") (pinfunction "1_1") (pintype "passive"))
      (node (ref "R7") (pin "2") (pinfunction "2_2") (pintype "passive"))
    )
    (net (code "31") (name "Net-(C16-Pad1)") (class "Default")
      (node (ref "C16") (pin "1") (pinfunction "1_1") (pintype "passive"))
      (node (ref "J8") (pin "12") (pinfunction "12_12") (pintype "bidirectional"))
    )
    (net (code "32") (name "Net-(C16-Pad2)") (class "Default")
      (node (ref "C16") (pin "2") (pinfunction "2_2") (pintype "passive"))
      (node (ref "J8") (pin "13") (pinfunction "13_13") (pintype "bidirectional"))
    )
    (net (code "33") (name "Net-(C17-Pad1)") (class "Default")
      (node (ref "C17") (pin "1") (pinfunction "1_1") (pintype "passive"))
      (node (ref "J8") (pin "5") (pinfunction "5_5") (pintype "bidirectional"))
    )
    (net (code "34") (name "Net-(C41-Pad1)") (class "Default")
      (node (ref "C41") (pin "1") (pinfunction "1_1") (pintype "passive"))
      (node (ref "R18") (pin "1") (pinfunction "1_1") (pintype "passive"))
      (node (ref "R20") (pin "2") (pinfunction "2_2") (pintype "passive"))
    )
    (net (code "35") (name "Net-(C42-Pad1)") (class "Default")
      (node (ref "C42") (pin "1") (pinfunction "1_1") (pintype "passive"))
      (node (ref "R17") (pin "1") (pinfunction "1_1") (pintype "passive"))
      (node (ref "R19") (pin "2") (pinfunction "2_2") (pintype "passive"))
    )
    (net (code "36") (name "Net-(D1-A)") (class "Default")
      (node (ref "D1") (pin "2") (pinfunction "A_2") (pintype "bidirectional"))
      (node (ref "JP1") (pin "1") (pinfunction "1_1") (pintype "passive"))
      (node (ref "JP1") (pin "2") (pinfunction "2_2") (pintype "passive"))
    )
    (net (code "37") (name "Net-(D1-K)") (class "Default")
      (node (ref "C35") (pin "+") (pinfunction "+_+") (pintype "passive"))
      (node (ref "D1") (pin "1") (pinfunction "K_1") (pintype "bidirectional"))
      (node (ref "L2") (pin "1") (pinfunction "1_1") (pintype "passive"))
      (node (ref "L3") (pin "1") (pinfunction "1_1") (pintype "passive"))
      (node (ref "L4") (pin "1") (pinfunction "1_1") (pintype "passive"))
    )
    (net (code "38") (name "Net-(D2-A)") (class "Default")
      (node (ref "D2") (pin "2") (pinfunction "A_2") (pintype "bidirectional"))
      (node (ref "L1") (pin "1") (pinfunction "1_1") (pintype "passive"))
    )
    (net (code "39") (name "Net-(D2-K)") (class "Default")
      (node (ref "D2") (pin "1") (pinfunction "K_1") (pintype "bidirectional"))
      (node (ref "JP1") (pin "10") (pinfunction "10_10") (pintype "passive"))
      (node (ref "JP1") (pin "9") (pinfunction "9_9") (pintype "passive"))
    )
    (net (code "40") (name "Net-(IC1-CAPM)") (class "Default")
      (node (ref "C7") (pin "2") (pinfunction "2_2") (pintype "passive"))
      (node (ref "IC1") (pin "4") (pinfunction "CAPM_4") (pintype "bidirectional"))
    )
    (net (code "41") (name "Net-(IC1-CAPP)") (class "Default")
      (node (ref "C7") (pin "1") (pinfunction "1_1") (pintype "passive"))
      (node (ref "IC1") (pin "2") (pinfunction "CAPP_2") (pintype "bidirectional"))
    )
    (net (code "42") (name "Net-(IC1-LDOO)") (class "Default")
      (node (ref "C8") (pin "1") (pinfunction "1_1") (pintype "passive"))
      (node (ref "IC1") (pin "18") (pinfunction "LDOO_18") (pintype "bidirectional"))
    )
    (net (code "43") (name "Net-(IC1-OUTL)") (class "Default")
      (node (ref "IC1") (pin "6") (pinfunction "OUTL_6") (pintype "output"))
      (node (ref "R19") (pin "1") (pinfunction "1_1") (pintype "passive"))
    )
    (net (code "44") (name "Net-(IC1-OUTR)") (class "Default")
      (node (ref "IC1") (pin "7") (pinfunction "OUTR_7") (pintype "output"))
      (node (ref "R20") (pin "1") (pinfunction "1_1") (pintype "passive"))
    )
    (net (code "45") (name "Net-(IC1-VNEG)") (class "Default")
      (node (ref "C6") (pin "1") (pinfunction "1_1") (pintype "passive"))
      (node (ref "IC1") (pin "5") (pinfunction "VNEG_5") (pintype "input"))
    )
    (net (code "46") (name "Net-(IC2-PD0{slash}OSC_IN)") (class "Default")
      (node (ref "IC2") (pin "5") (pinfunction "PD0/OSC_IN_5") (pintype "bidirectional"))
      (node (ref "R6") (pin "1") (pinfunction "1_1") (pintype "passive"))
    )
    (net (code "47") (name "Net-(IC2-PD1{slash}OSC_OUT)") (class "Default")
      (node (ref "IC2") (pin "6") (pinfunction "PD1/OSC_OUT_6") (pintype "bidirectional"))
      (node (ref "R7") (pin "1") (pinfunction "1_1") (pintype "passive"))
    )
    (net (code "48") (name "Net-(IC2-VCAP_1)") (class "Default")
      (node (ref "C1") (pin "1") (pinfunction "1_1") (pintype "passive"))
      (node (ref "IC2") (pin "31") (pinfunction "VCAP_1_31") (pintype "power_in"))
    )
    (net (code "49") (name "Net-(IC2-VCAP_2)") (class "Default")
      (node (ref "C2") (pin "1") (pinfunction "1_1") (pintype "passive"))
      (node (ref "IC2") (pin "47") (pinfunction "VCAP_2_47") (pintype "power_in"))
    )
    (net (code "50") (name "Net-(IC3-Pad3)") (class "Default")
      (node (ref "IC3") (pin "3") (pinfunction "3_3") (pintype "bidirectional"))
      (node (ref "R10") (pin "2") (pinfunction "2_2") (pintype "passive"))
    )
    (net (code "51") (name "Net-(IC4-Pad3)") (class "Default")
      (node (ref "IC4") (pin "3") (pinfunction "3_3") (pintype "bidirectional"))
      (node (ref "R11") (pin "2") (pinfunction "2_2") (pintype "passive"))
    )
    (net (code "52") (name "Net-(IC9-INPUT)") (class "Default")
      (node (ref "C37") (pin "+") (pinfunction "+_+") (pintype "passive"))
      (node (ref "IC9") (pin "3") (pinfunction "INPUT_3") (pintype "input"))
      (node (ref "L4") (pin "2") (pinfunction "2_2") (pintype "passive"))
    )
    (net (code "53") (name "Net-(IC10-VIN)") (class "Default")
      (node (ref "C33") (pin "+") (pinfunction "+_+") (pintype "passive"))
      (node (ref "IC10") (pin "3") (pinfunction "VIN_3") (pintype "bidirectional"))
      (node (ref "L3") (pin "2") (pinfunction "2_2") (pintype "passive"))
    )
    (net (code "54") (name "Net-(J1-3)") (class "Default")
      (node (ref "J1") (pin "P3") (pinfunction "3_P3") (pintype "passive"))
      (node (ref "R16") (pin "2") (pinfunction "2_2") (pintype "passive"))
    )
    (net (code "55") (name "Net-(J2-3)") (class "Default")
      (node (ref "J2") (pin "P3") (pinfunction "3_P3") (pintype "passive"))
      (node (ref "R15") (pin "2") (pinfunction "2_2") (pintype "passive"))
    )
    (net (code "56") (name "Net-(J3-3)") (class "Default")
      (node (ref "C50") (pin "1") (pinfunction "1_1") (pintype "passive"))
      (node (ref "J3") (pin "P3") (pinfunction "3_P3") (pintype "passive"))
      (node (ref "R22") (pin "1") (pinfunction "1_1") (pintype "passive"))
    )
    (net (code "57") (name "Net-(J4-3)") (class "Default")
      (node (ref "C48") (pin "1") (pinfunction "1_1") (pintype "passive"))
      (node (ref "J4") (pin "P3") (pinfunction "3_P3") (pintype "passive"))
      (node (ref "R27") (pin "1") (pinfunction "1_1") (pintype "passive"))
    )
    (net (code "58") (name "Net-(J5-3)") (class "Default")
      (node (ref "C46") (pin "1") (pinfunction "1_1") (pintype "passive"))
      (node (ref "J5") (pin "P3") (pinfunction "3_P3") (pintype "passive"))
      (node (ref "R24") (pin "1") (pinfunction "1_1") (pintype "passive"))
    )
    (net (code "59") (name "Net-(J6-3)") (class "Default")
      (node (ref "C44") (pin "1") (pinfunction "1_1") (pintype "passive"))
      (node (ref "J6") (pin "P3") (pinfunction "3_P3") (pintype "passive"))
      (node (ref "R21") (pin "1") (pinfunction "1_1") (pintype "passive"))
    )
    (net (code "60") (name "Net-(Q1B-2)") (class "Default")
      (node (ref "C4") (pin "1") (pinfunction "1_1") (pintype "passive"))
      (node (ref "Q1") (pin "3") (pinfunction "2_3") (pintype "passive"))
      (node (ref "R6") (pin "2") (pinfunction "2_2") (pintype "passive"))
    )
    (net (code "61") (name "OUT1") (class "Default")
      (node (ref "C39") (pin "2") (pinfunction "2_2") (pintype "passive"))
      (node (ref "IC7") (pin "1") (pinfunction "1OUT_1") (pintype "bidirectional"))
      (node (ref "R13") (pin "2") (pinfunction "2_2") (pintype "passive"))
      (node (ref "R16") (pin "1") (pinfunction "1_1") (pintype "passive"))
    )
    (net (code "62") (name "OUT2") (class "Default")
      (node (ref "C40") (pin "2") (pinfunction "2_2") (pintype "passive"))
      (node (ref "IC7") (pin "7") (pinfunction "2OUT_7") (pintype "bidirectional"))
      (node (ref "R14") (pin "2") (pinfunction "2_2") (pintype "passive"))
      (node (ref "R15") (pin "1") (pinfunction "1_1") (pintype "passive"))
    )
    (net (code "63") (name "RESET") (class "Default")
      (node (ref "C3") (pin "1") (pinfunction "1_1") (pintype "passive"))
      (node (ref "IC2") (pin "7") (pinfunction "NRST_7") (pintype "bidirectional"))
      (node (ref "R5") (pin "1") (pinfunction "1_1") (pintype "passive"))
    )
    (net (code "64") (name "ROM_CS_1") (class "Default")
      (node (ref "IC2") (pin "17") (pinfunction "PA3/USART2_RX/ADC3/TIM2_CH4_17") (pintype "bidirectional"))
      (node (ref "IC3") (pin "1") (pinfunction "1_1") (pintype "bidirectional"))
      (node (ref "R8") (pin "1") (pinfunction "1_1") (pintype "passive"))
    )
    (net (code "65") (name "ROM_CS_2") (class "Default")
      (node (ref "IC2") (pin "20") (pinfunction "PA4/SPI1_NSS/SPI3_NSS/USART2_CK/I2S3_WS/ADC4/DAC1_20") (pintype "bidirectional"))
      (node (ref "IC4") (pin "1") (pinfunction "1_1") (pintype "bidirectional"))
      (node (ref "R9") (pin "1") (pinfunction "1_1") (pintype "passive"))
    )
    (net (code "66") (name "ROM_MISO") (class "Default")
      (node (ref "IC2") (pin "22") (pinfunction "PA6/SPI1_MISO/ADC6/TIM3_CH1_22") (pintype "bidirectional"))
      (node (ref "IC3") (pin "2") (pinfunction "2_2") (pintype "bidirectional"))
      (node (ref "IC4") (pin "2") (pinfunction "2_2") (pintype "bidirectional"))
    )
    (net (code "67") (name "ROM_MOSI") (class "Default")
      (node (ref "IC2") (pin "23") (pinfunction "PA7/SPI1_MOSI/ADC7/TIM3_CH2_23") (pintype "bidirectional"))
      (node (ref "IC3") (pin "5") (pinfunction "5_5") (pintype "bidirectional"))
      (node (ref "IC4") (pin "5") (pinfunction "5_5") (pintype "bidirectional"))
    )
    (net (code "68") (name "ROM_SCK") (class "Default")
      (node (ref "IC2") (pin "21") (pinfunction "PA5/SPI1_SCK/ADC5/DAC2_21") (pintype "bidirectional"))
      (node (ref "IC3") (pin "6") (pinfunction "6_6") (pintype "bidirectional"))
      (node (ref "IC4") (pin "6") (pinfunction "6_6") (pintype "bidirectional"))
    )
    (net (code "69") (name "SWCLK") (class "Default")
      (node (ref "IC2") (pin "49") (pinfunction "PA14/JTCK-SWCLK_49") (pintype "bidirectional"))
      (node (ref "J7") (pin "3") (pinfunction "3_3") (pintype "passive"))
    )
    (net (code "70") (name "SWDIO") (class "Default")
      (node (ref "IC2") (pin "46") (pinfunction "PA13/JTMS-SWDAT_46") (pintype "bidirectional"))
      (node (ref "J7") (pin "2") (pinfunction "2_2") (pintype "passive"))
    )
    (net (code "71") (name "VCC") (class "Default")
      (node (ref "C29") (pin "+") (pinfunction "+_+") (pintype "passive"))
      (node (ref "C30") (pin "1") (pinfunction "1_1") (pintype "passive"))
      (node (ref "IC7") (pin "8") (pinfunction "VCC+_8") (pintype "bidirectional"))
      (node (ref "L2") (pin "2") (pinfunction "2_2") (pintype "passive"))
    )
    (net (code "72") (name "VEE") (class "Default")
      (node (ref "C28") (pin "2") (pinfunction "2_2") (pintype "passive"))
      (node (ref "C31") (pin "-") (pinfunction "-_-") (pintype "passive"))
      (node (ref "IC7") (pin "4") (pinfunction "VCC-_4") (pintype "bidirectional"))
      (node (ref "L1") (pin "2") (pinfunction "2_2") (pintype "passive"))
      (node (ref "R12") (pin "1") (pinfunction "1_1") (pintype "passive"))
    )
    (net (code "73") (name "VINA-") (class "Default")
      (node (ref "C45") (pin "1") (pinfunction "1_1") (pintype "passive"))
      (node (ref "IC5") (pin "2") (pinfunction "VINA-_2") (pintype "bidirectional"))
      (node (ref "R21") (pin "2") (pinfunction "2_2") (pintype "passive"))
      (node (ref "R23") (pin "1") (pinfunction "1_1") (pintype "passive"))
    )
    (net (code "74") (name "VINB-") (class "Default")
      (node (ref "C47") (pin "1") (pinfunction "1_1") (pintype "passive"))
      (node (ref "IC5") (pin "6") (pinfunction "VINB-_6") (pintype "bidirectional"))
      (node (ref "R24") (pin "2") (pinfunction "2_2") (pintype "passive"))
      (node (ref "R25") (pin "2") (pinfunction "2_2") (pintype "passive"))
      (node (ref "R26") (pin "1") (pinfunction "1_1") (pintype "passive"))
    )
    (net (code "75") (name "VINC-") (class "Default")
      (node (ref "C49") (pin "1") (pinfunction "1_1") (pintype "passive"))
      (node (ref "IC5") (pin "9") (pinfunction "VINC-_9") (pintype "bidirectional"))
      (node (ref "R27") (pin "2") (pinfunction "2_2") (pintype "passive"))
      (node (ref "R28") (pin "2") (pinfunction "2_2") (pintype "passive"))
      (node (ref "R29") (pin "1") (pinfunction "1_1") (pintype "passive"))
    )
    (net (code "76") (name "VIND-") (class "Default")
      (node (ref "C51") (pin "1") (pinfunction "1_1") (pintype "passive"))
      (node (ref "IC5") (pin "13") (pinfunction "VIND-_13") (pintype "bidirectional"))
      (node (ref "R22") (pin "2") (pinfunction "2_2") (pintype "passive"))
      (node (ref "R31") (pin "2") (pinfunction "2_2") (pintype "passive"))
      (node (ref "R32") (pin "1") (pinfunction "1_1") (pintype "passive"))
    )
    (net (code "77") (name "unconnected-(IC2-PA0-WKUP{slash}USART2_CTS{slash}UART4_TX{slash}ADC0{slash}TIM2_CH1_ETR-Pad14)") (class "Default")
      (node (ref "IC2") (pin "14") (pinfunction "PA0-WKUP/USART2_CTS/UART4_TX/ADC0/TIM2_CH1_ETR_14") (pintype "bidirectional"))
    )
    (net (code "78") (name "unconnected-(IC2-PA1{slash}USART2_RTS{slash}UART4_RX{slash}ADC1{slash}TIM2_CH2-Pad15)") (class "Default")
      (node (ref "IC2") (pin "15") (pinfunction "PA1/USART2_RTS/UART4_RX/ADC1/TIM2_CH2_15") (pintype "bidirectional"))
    )
    (net (code "79") (name "unconnected-(IC2-PA2{slash}USART2_TX{slash}ADC2{slash}TIM2_CH3-Pad16)") (class "Default")
      (node (ref "IC2") (pin "16") (pinfunction "PA2/USART2_TX/ADC2/TIM2_CH3_16") (pintype "bidirectional"))
    )
    (net (code "80") (name "unconnected-(IC2-PA8{slash}USART1_CK{slash}TIM1_CH1{slash}MCO-Pad41)") (class "Default")
      (node (ref "IC2") (pin "41") (pinfunction "PA8/USART1_CK/TIM1_CH1/MCO_41") (pintype "bidirectional"))
    )
    (net (code "81") (name "unconnected-(IC2-PA9{slash}USART1_TX{slash}TIM1_CH2-Pad42)") (class "Default")
      (node (ref "IC2") (pin "42") (pinfunction "PA9/USART1_TX/TIM1_CH2_42") (pintype "bidirectional"))
    )
    (net (code "82") (name "unconnected-(IC2-PA10{slash}USART1_RX{slash}TIM1_CH3-Pad43)") (class "Default")
      (node (ref "IC2") (pin "43") (pinfunction "PA10/USART1_RX/TIM1_CH3_43") (pintype "bidirectional"))
    )
    (net (code "83") (name "unconnected-(IC2-PA11{slash}USART1_CTS{slash}CANRX{slash}USBDM{slash}TIM1_CH4-Pad44)") (class "Default")
      (node (ref "IC2") (pin "44") (pinfunction "PA11/USART1_CTS/CANRX/USBDM/TIM1_CH4_44") (pintype "bidirectional"))
    )
    (net (code "84") (name "unconnected-(IC2-PA12{slash}USART1_RTS{slash}CANTX{slash}USBDP{slash}TIM1_ETR-Pad45)") (class "Default")
      (node (ref "IC2") (pin "45") (pinfunction "PA12/USART1_RTS/CANTX/USBDP/TIM1_ETR_45") (pintype "bidirectional"))
    )
    (net (code "85") (name "unconnected-(IC2-PB7{slash}I2C1_SDA{slash}TIM4_CH2{slash}USART1_RX-Pad59)") (class "Default")
      (node (ref "IC2") (pin "59") (pinfunction "PB7/I2C1_SDA/TIM4_CH2/USART1_RX_59") (pintype "bidirectional"))
    )
    (net (code "86") (name "unconnected-(IC2-PB8{slash}TIM4_CH3{slash}I2C1_SCL-Pad61)") (class "Default")
      (node (ref "IC2") (pin "61") (pinfunction "PB8/TIM4_CH3/I2C1_SCL_61") (pintype "bidirectional"))
    )
    (net (code "87") (name "unconnected-(IC2-PB9{slash}SPI2_NSS{slash}I2S2_WS{slash}I2C1_SDA{slash}TIM4_CH4-Pad62)") (class "Default")
      (node (ref "IC2") (pin "62") (pinfunction "PB9/SPI2_NSS/I2S2_WS/I2C1_SDA/TIM4_CH4_62") (pintype "bidirectional"))
    )
    (net (code "88") (name "unconnected-(IC2-PB10{slash}SPI2_SCK{slash}I2S_SCK{slash}I2C2_SCL{slash}USART3_TX-Pad29)") (class "Default")
      (node (ref "IC2") (pin "29") (pinfunction "PB10/SPI2_SCK/I2S_SCK/I2C2_SCL/USART3_TX_29") (pintype "bidirectional"))
    )
    (net (code "89") (name "unconnected-(IC2-PB11{slash}I2C2_SDA{slash}USART3_RX-Pad30)") (class "Default")
      (node (ref "IC2") (pin "30") (pinfunction "PB11/I2C2_SDA/USART3_RX_30") (pintype "bidirectional"))
    )
    (net (code "90") (name "unconnected-(IC2-PB14{slash}SPI2_MISO{slash}USART3_RTS{slash}TIM1_CH2N-Pad35)") (class "Default")
      (node (ref "IC2") (pin "35") (pinfunction "PB14/SPI2_MISO/USART3_RTS/TIM1_CH2N_35") (pintype "bidirectional"))
    )
    (net (code "91") (name "unconnected-(IC2-PC6{slash}I2S2_MCK-Pad37)") (class "Default")
      (node (ref "IC2") (pin "37") (pinfunction "PC6/I2S2_MCK_37") (pintype "bidirectional"))
    )
    (net (code "92") (name "unconnected-(IC2-PC8-Pad39)") (class "Default")
      (node (ref "IC2") (pin "39") (pinfunction "PC8_39") (pintype "bidirectional"))
    )
    (net (code "93") (name "unconnected-(IC2-PC9{slash}I2S2_CKIN{slash}I2S3_CKIN-Pad40)") (class "Default")
      (node (ref "IC2") (pin "40") (pinfunction "PC9/I2S2_CKIN/I2S3_CKIN_40") (pintype "bidirectional"))
    )
    (net (code "94") (name "unconnected-(IC2-PD2{slash}TIM3-ETR-Pad54)") (class "Default")
      (node (ref "IC2") (pin "54") (pinfunction "PD2/TIM3-ETR_54") (pintype "bidirectional"))
    )
    (net (code "95") (name "unconnected-(IC8-NC-Pad3)") (class "Default")
      (node (ref "IC8") (pin "3") (pinfunction "NC_3") (pintype "no_connect"))
    )
    (net (code "96") (name "unconnected-(J1-2-PadP2)") (class "Default")
      (node (ref "J1") (pin "P2") (pinfunction "2_P2") (pintype "passive"))
    )
    (net (code "97") (name "unconnected-(J2-2-PadP2)") (class "Default")
      (node (ref "J2") (pin "P2") (pinfunction "2_P2") (pintype "passive"))
    )
    (net (code "98") (name "unconnected-(J8-Pad1)") (class "Default")
      (node (ref "J8") (pin "1") (pinfunction "1_1") (pintype "bidirectional"))
    )
    (net (code "99") (name "unconnected-(J8-Pad4)") (class "Default")
      (node (ref "J8") (pin "4") (pinfunction "4_4") (pintype "bidirectional"))
    )
    (net (code "100") (name "unconnected-(J8-Pad6)") (class "Default")
      (node (ref "J8") (pin "6") (pinfunction "6_6") (pintype "bidirectional"))
    )
    (net (code "101") (name "unconnected-(J8-Pad7)") (class "Default")
      (node (ref "J8") (pin "7") (pinfunction "7_7") (pintype "bidirectional"))
    )
    (net (code "102") (name "unconnected-(J8-Pad8)") (class "Default")
      (node (ref "J8") (pin "8") (pinfunction "8_8") (pintype "bidirectional"))
    )
    (net (code "103") (name "unconnected-(J8-Pad9)") (class "Default")
      (node (ref "J8") (pin "9") (pinfunction "9_9") (pintype "bidirectional"))
    )
    (net (code "104") (name "unconnected-(J8-Pad10)") (class "Default")
      (node (ref "J8") (pin "10") (pinfunction "10_10") (pintype "bidirectional"))
    )
    (net (code "105") (name "unconnected-(J8-Pad11)") (class "Default")
      (node (ref "J8") (pin "11") (pinfunction "11_11") (pintype "bidirectional"))
    )
    (net (code "106") (name "unconnected-(J8-Pad14)") (class "Default")
      (node (ref "J8") (pin "14") (pinfunction "14_14") (pintype "bidirectional"))
    )
    (net (code "107") (name "unconnected-(J8-Pad15)") (class "Default")
      (node (ref "J8") (pin "15") (pinfunction "15_15") (pintype "bidirectional"))
    )
    (net (code "108") (name "unconnected-(J8-PadMP1)") (class "Default")
      (node (ref "J8") (pin "MP1") (pinfunction "MP1_MP1") (pintype "bidirectional"))
    )
    (net (code "109") (name "unconnected-(J8-PadMP2)") (class "Default")
      (node (ref "J8") (pin "MP2") (pinfunction "MP2_MP2") (pintype "bidirectional"))
    )
  )
)
